# main.net
KiCad netlist of a schematic drawn in Altium Designer
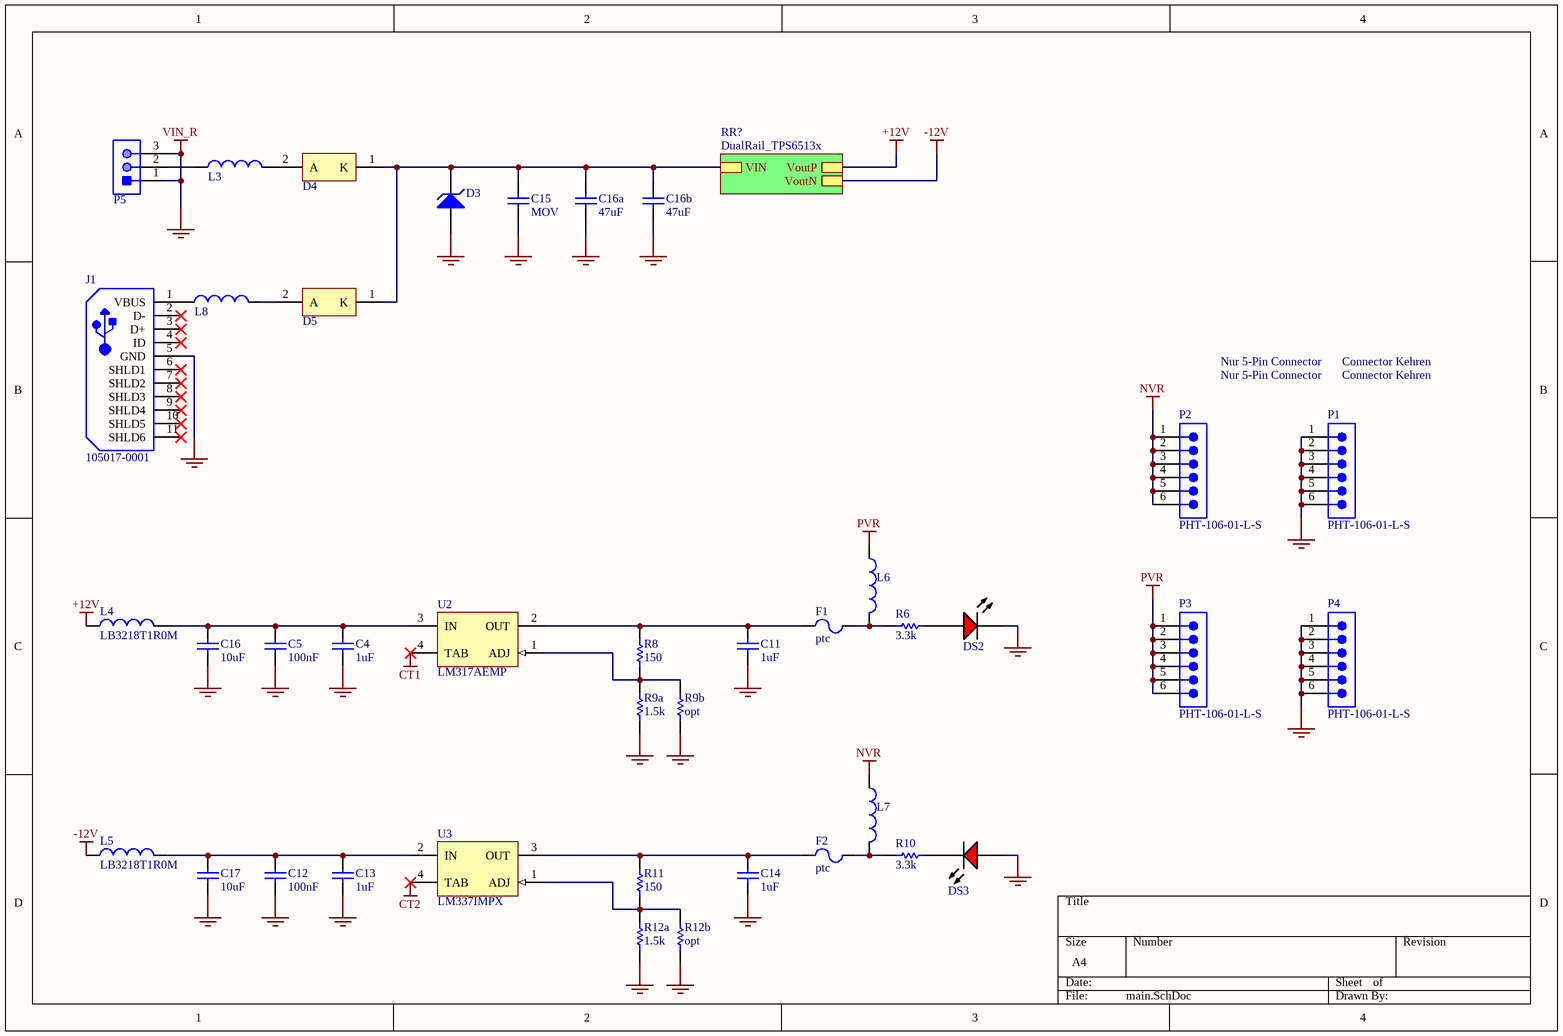
[diagram p0: main.SchDoc]

(export (version "E")
  (design (tool "Eeschema 10.0.6"))
  (components
    (comp (ref "C4")
      (value "1uF")
      (footprint "CAPC0603(1608)100_L")
      (description "CAP 1uF 25V ±20% 0603 (1608 Metric) Thickness 1mm SMD")
      (fields (field (name "TOLERANCE") "Â±20%"))
      (libsource (lib "Altium Content Vault") (part "CAP"))
    )
    (comp (ref "C5")
      (value "100nF")
      (footprint "CAPC0603(1608)100_L")
      (description "CAP 100nF 25V ±20% 0603 (1608 Metric) Thickness 1mm SMD")
      (fields (field (name "TOLERANCE") "Â±20%"))
      (libsource (lib "Altium Content Vault") (part "CAP"))
    )
    (comp (ref "C11")
      (value "1uF")
      (footprint "CAPC0603(1608)100_L")
      (description "CAP 1uF 25V ±20% 0603 (1608 Metric) Thickness 1mm SMD")
      (fields (field (name "TOLERANCE") "Â±20%"))
      (libsource (lib "Altium Content Vault") (part "CAP"))
    )
    (comp (ref "C12")
      (value "100nF")
      (footprint "CAPC0603(1608)100_L")
      (description "CAP 100nF 25V ±20% 0603 (1608 Metric) Thickness 1mm SMD")
      (fields (field (name "TOLERANCE") "Â±20%"))
      (libsource (lib "Altium Content Vault") (part "CAP"))
    )
    (comp (ref "C13")
      (value "1uF")
      (footprint "CAPC0603(1608)100_L")
      (description "CAP 1uF 25V ±20% 0603 (1608 Metric) Thickness 1mm SMD")
      (fields (field (name "TOLERANCE") "Â±20%"))
      (libsource (lib "Altium Content Vault") (part "CAP"))
    )
    (comp (ref "C14")
      (value "1uF")
      (footprint "CAPC0603(1608)100_L")
      (description "CAP 1uF 25V ±20% 0603 (1608 Metric) Thickness 1mm SMD")
      (fields (field (name "TOLERANCE") "Â±20%"))
      (libsource (lib "Altium Content Vault") (part "CAP"))
    )
    (comp (ref "C15")
      (value "MOV")
      (footprint "CAPC0805(2012)75_L")
      (description "MOV 0805")
      (fields (field (name "TOLERANCE") "Â±20%"))
      (libsource (lib "Altium Content Vault") (part "CAP"))
    )
    (comp (ref "C16")
      (value "10uF")
      (footprint "CAPC1206(3216)190_L")
      (description "CAP 4.7uF 25V ±20% 1206 (3216 Metric) Thickness 1.9mm SMD")
      (fields (field (name "TOLERANCE") "Â±20%"))
      (libsource (lib "Altium Content Vault") (part "CAP"))
    )
    (comp (ref "C16a")
      (value "47uF")
      (footprint "CAPC1206(3216)190_L")
      (description "CAP 47uF 10V ±20% 1206 X5R")
      (fields (field (name "TOLERANCE") "Â±20%"))
      (libsource (lib "Altium Content Vault") (part "CAP"))
    )
    (comp (ref "C16b")
      (value "47uF")
      (footprint "CAPC1206(3216)190_L")
      (description "CAP 47uF 10V ±20% 1206 X5R")
      (fields (field (name "TOLERANCE") "Â±20%"))
      (libsource (lib "Altium Content Vault") (part "CAP"))
    )
    (comp (ref "C17")
      (value "10uF")
      (footprint "CAPC1206(3216)190_L")
      (description "CAP 4.7uF 25V ±20% 1206 (3216 Metric) Thickness 1.9mm SMD")
      (fields (field (name "TOLERANCE") "Â±20%"))
      (libsource (lib "Altium Content Vault") (part "CAP"))
    )
    (comp (ref "D3")
      (value "Q6 - btz52c5v6")
      (footprint "DIOD-SOD123-2_V")
      (description "Zener Diode 500mw, 5.6v")
      (fields (field (name "MANUFACTURER") "Diodes Inc") (field (name "PARTNUMBER") "BZT52C16-7-F"))
      (libsource (lib "Altium Content Vault") (part "DIOD-DZEN-A1K2-2"))
    )
    (comp (ref "D4")
      (value "MBRM120LT3")
      (footprint "ONSC-POWERMITE-2-457-04_D_V")
      (description "Schottky Power Rectifier, 2-Pin Powermite, Tape and Reel")
      (fields (field (name "MANUFACTURER") "On Semiconductor"))
      (libsource (lib "Altium Content Vault") (part "ONSC-D-K1A2-2_A"))
    )
    (comp (ref "D5")
      (value "MBRM120LT3")
      (footprint "ONSC-POWERMITE-2-457-04_D_V")
      (description "Schottky Power Rectifier, 2-Pin Powermite, Tape and Reel")
      (fields (field (name "MANUFACTURER") "On Semiconductor"))
      (libsource (lib "Altium Content Vault") (part "ONSC-D-K1A2-2_A"))
    )
    (comp (ref "DS2")
      (value "TLMS1100-GS08")
      (footprint "VISH-TLMX1100_V")
      (description "LED, RED, 2.1 V, -40 to 100 degC, 2-Pin SMD (0603), RoHS, Tape and Reel")
      (fields (field (name "TOLERANCE") "5%"))
      (libsource (lib "Altium Content Vault") (part "LED-RED-AK-2"))
    )
    (comp (ref "DS3")
      (value "TLMS1100-GS08")
      (footprint "VISH-TLMX1100_V")
      (description "LED, RED, 2.1 V, -40 to 100 degC, 2-Pin SMD (0603), RoHS, Tape and Reel")
      (fields (field (name "TOLERANCE") "5%"))
      (libsource (lib "Altium Content Vault") (part "LED-RED-AK-2"))
    )
    (comp (ref "F1")
      (value "ptc")
      (footprint "LFUS-1206L012WR_V")
      (description "200mA PTC")
      (fields (field (name "MANUFACTURER") "Littelfuse"))
      (libsource (lib "Altium Content Vault") (part "FUSE-2"))
    )
    (comp (ref "F2")
      (value "ptc")
      (footprint "LFUS-1206L012WR_V")
      (description "200mA PTC")
      (fields (field (name "MANUFACTURER") "Littelfuse"))
      (libsource (lib "Altium Content Vault") (part "FUSE-2"))
    )
    (comp (ref "J1")
      (value "105017-0001")
      (footprint "USB-MICRO-B_V")
      (fields (field (name "MANUFACTURER") "Molex"))
      (libsource (lib "Altium Content Vault") (part "USB-5-6SHLD"))
    )
    (comp (ref "L3")
      (value "FBMJ2125HM210NT")
      (footprint "INDC2013X105X50LL20T30")
      (description "Chip Inductor, 21 Ohm, +/- 30%, 6 A, -40 to 125 degC, 0805 (2012 Metric), RoHS, Tape and Reel")
      (fields (field (name "TOLERANCE") "30%"))
      (libsource (lib "Altium Content Vault") (part "IND-2"))
    )
    (comp (ref "L4")
      (value "LB3218T1R0M")
      (footprint "TDK-B82422A1103K100_V")
      (description "FIXED IND 1UH 1.075A 60 MOHM SMD")
      (fields (field (name "TOLERANCE") "±10%") (field (name "MANUFACTURER") "EPCOS-(TDK)"))
      (libsource (lib "Altium Content Vault") (part "IND-2"))
    )
    (comp (ref "L5")
      (value "LB3218T1R0M")
      (footprint "TDK-B82422A1103K100_V")
      (description "FIXED IND 1UH 1.075A 60 MOHM SMD")
      (fields (field (name "TOLERANCE") "±10%") (field (name "MANUFACTURER") "EPCOS-(TDK)"))
      (libsource (lib "Altium Content Vault") (part "IND-2"))
    )
    (comp (ref "L6")
      (value "FBMJ2125HM210NT")
      (footprint "INDC2013X105X50LL20T30")
      (description "Chip Inductor, 21 Ohm, +/- 30%, 6 A, -40 to 125 degC, 0805 (2012 Metric), RoHS, Tape and Reel")
      (fields (field (name "TOLERANCE") "30%"))
      (libsource (lib "Altium Content Vault") (part "IND-2"))
    )
    (comp (ref "L7")
      (value "FBMJ2125HM210NT")
      (footprint "INDC2013X105X50LL20T30")
      (description "Chip Inductor, 21 Ohm, +/- 30%, 6 A, -40 to 125 degC, 0805 (2012 Metric), RoHS, Tape and Reel")
      (fields (field (name "TOLERANCE") "30%"))
      (libsource (lib "Altium Content Vault") (part "IND-2"))
    )
    (comp (ref "L8")
      (value "FBMJ2125HM210NT")
      (footprint "INDC2013X105X50LL20T30")
      (description "Chip Inductor, 21 Ohm, +/- 30%, 6 A, -40 to 125 degC, 0805 (2012 Metric), RoHS, Tape and Reel")
      (fields (field (name "TOLERANCE") "30%"))
      (libsource (lib "Altium Content Vault") (part "IND-2"))
    )
    (comp (ref "P1")
      (value "PHT-106-01-L-S")
      (footprint "SMTC-PHT-106-01-X-S")
      (description "Press Fit Header, Through-hole, Vertical, -55 to 125 degC, 2.54 mm Pitch, 6-Pin, Male, RoHS")
      (fields (field (name "MANUFACTURER") "Samtec"))
      (libsource (lib "Altium Content Vault") (part "SMTC-PHT-106-01-X-S"))
    )
    (comp (ref "P2")
      (value "PHT-106-01-L-S")
      (footprint "SMTC-PHT-106-01-X-S")
      (description "Press Fit Header, Through-hole, Vertical, -55 to 125 degC, 2.54 mm Pitch, 6-Pin, Male, RoHS")
      (fields (field (name "MANUFACTURER") "Samtec"))
      (libsource (lib "Altium Content Vault") (part "SMTC-PHT-106-01-X-S"))
    )
    (comp (ref "P3")
      (value "PHT-106-01-L-S")
      (footprint "SMTC-PHT-106-01-X-S")
      (description "Press Fit Header, Through-hole, Vertical, -55 to 125 degC, 2.54 mm Pitch, 6-Pin, Male, RoHS")
      (fields (field (name "MANUFACTURER") "Samtec"))
      (libsource (lib "Altium Content Vault") (part "SMTC-PHT-106-01-X-S"))
    )
    (comp (ref "P4")
      (value "PHT-106-01-L-S")
      (footprint "SMTC-PHT-106-01-X-S")
      (description "Press Fit Header, Through-hole, Vertical, -55 to 125 degC, 2.54 mm Pitch, 6-Pin, Male, RoHS")
      (fields (field (name "MANUFACTURER") "Samtec"))
      (libsource (lib "Altium Content Vault") (part "SMTC-PHT-106-01-X-S"))
    )
    (comp (ref "P5")
      (value "22-23-2031")
      (footprint "MOLX-22-23-2031_V")
      (description "Male Header, Pitch 2.54 mm, 1 x 3 Position, Height 8.18 mm, Tail Length 3.56 mm, RoHS, Bulk")
      (fields (field (name "MANUFACTURER") "Molex"))
      (libsource (lib "Altium Content Vault") (part "CN-1P-M-R3"))
    )
    (comp (ref "R6")
      (value "3.3k")
      (footprint "RESC0603(1608)_L")
      (fields (field (name "TOLERANCE") "1 %") (field (name "POWER") "0.1 W"))
      (libsource (lib "Altium Content Vault") (part "RES"))
    )
    (comp (ref "R8")
      (value "150")
      (footprint "RESC0603(1608)_L")
      (fields (field (name "TOLERANCE") "1 %") (field (name "POWER") "0.1 W"))
      (libsource (lib "Altium Content Vault") (part "RES"))
    )
    (comp (ref "R9a")
      (value "1.5k")
      (footprint "RESC0603(1608)_L")
      (fields (field (name "TOLERANCE") "1 %") (field (name "POWER") "0.1 W"))
      (libsource (lib "Altium Content Vault") (part "RES"))
    )
    (comp (ref "R9b")
      (value "opt")
      (footprint "RESC0603(1608)_L")
      (fields (field (name "TOLERANCE") "1 %") (field (name "POWER") "0.1 W"))
      (libsource (lib "Altium Content Vault") (part "RES"))
    )
    (comp (ref "R10")
      (value "3.3k")
      (footprint "RESC0603(1608)_L")
      (fields (field (name "TOLERANCE") "1 %") (field (name "POWER") "0.1 W"))
      (libsource (lib "Altium Content Vault") (part "RES"))
    )
    (comp (ref "R11")
      (value "150")
      (footprint "RESC0603(1608)_L")
      (fields (field (name "TOLERANCE") "1 %") (field (name "POWER") "0.1 W"))
      (libsource (lib "Altium Content Vault") (part "RES"))
    )
    (comp (ref "R12a")
      (value "1.5k")
      (footprint "RESC0603(1608)_L")
      (fields (field (name "TOLERANCE") "1 %") (field (name "POWER") "0.1 W"))
      (libsource (lib "Altium Content Vault") (part "RES"))
    )
    (comp (ref "R12b")
      (value "opt")
      (footprint "RESC0603(1608)_L")
      (fields (field (name "TOLERANCE") "1 %") (field (name "POWER") "0.1 W"))
      (libsource (lib "Altium Content Vault") (part "RES"))
    )
    (comp (ref "U2")
      (value "LM317AEMP")
      (footprint "DCY0004A_N")
      (description "3-Terminal Adjustable Regulator, 4-pin SOT-223")
      (fields (field (name "MANUFACTURER") "Texas Instruments"))
      (libsource (lib "Altium Content Vault") (part "PM-REG-LM317ADJ-SOT4"))
    )
    (comp (ref "U3")
      (value "LM337IMPX")
      (footprint "MP04A_N")
      (description "3-Terminal Adjustable Negative Regulator, 4-pin SOT-223")
      (fields (field (name "MANUFACTURER") "National Semiconductor"))
      (libsource (lib "Altium Content Vault") (part "PM-REG-LM337ADJ-SOT4"))
    )
  )
  (nets
    (net (code "1") (name "+12V") (class "Default")
      (node (ref "L4") (pin "1") (pinfunction "1_1") (pintype "passive"))
    )
    (net (code "2") (name "-12V") (class "Default")
      (node (ref "L5") (pin "1") (pinfunction "1_1") (pintype "passive"))
    )
    (net (code "3") (name "/VIN") (class "Default")
      (node (ref "C15") (pin "2") (pinfunction "2_2") (pintype "passive"))
      (node (ref "C16a") (pin "2") (pinfunction "2_2") (pintype "passive"))
      (node (ref "C16b") (pin "2") (pinfunction "2_2") (pintype "passive"))
      (node (ref "D3") (pin "2") (pinfunction "K_2") (pintype "passive"))
      (node (ref "D4") (pin "1") (pinfunction "K_1") (pintype "passive"))
      (node (ref "D5") (pin "1") (pinfunction "K_1") (pintype "passive"))
    )
    (net (code "4") (name "CT1") (class "Default")
      (node (ref "U2") (pin "4") (pinfunction "TAB_4") (pintype "power_in"))
    )
    (net (code "5") (name "CT2") (class "Default")
      (node (ref "U3") (pin "4") (pinfunction "TAB_4") (pintype "power_in"))
    )
    (net (code "6") (name "GND") (class "Default")
      (node (ref "C11") (pin "1") (pinfunction "1_1") (pintype "passive"))
      (node (ref "C12") (pin "1") (pinfunction "1_1") (pintype "passive"))
      (node (ref "C13") (pin "1") (pinfunction "1_1") (pintype "passive"))
      (node (ref "C14") (pin "1") (pinfunction "1_1") (pintype "passive"))
      (node (ref "C15") (pin "1") (pinfunction "1_1") (pintype "passive"))
      (node (ref "C16") (pin "1") (pinfunction "1_1") (pintype "passive"))
      (node (ref "C16a") (pin "1") (pinfunction "1_1") (pintype "passive"))
      (node (ref "C16b") (pin "1") (pinfunction "1_1") (pintype "passive"))
      (node (ref "C17") (pin "1") (pinfunction "1_1") (pintype "passive"))
      (node (ref "C4") (pin "1") (pinfunction "1_1") (pintype "passive"))
      (node (ref "C5") (pin "1") (pinfunction "1_1") (pintype "passive"))
      (node (ref "D3") (pin "1") (pinfunction "A_1") (pintype "passive"))
      (node (ref "DS2") (pin "2") (pinfunction "K_2") (pintype "passive"))
      (node (ref "DS3") (pin "1") (pinfunction "A_1") (pintype "passive"))
      (node (ref "J1") (pin "5") (pinfunction "GND_5") (pintype "passive"))
      (node (ref "P1") (pin "1") (pinfunction "1_1") (pintype "passive"))
      (node (ref "P1") (pin "2") (pinfunction "2_2") (pintype "passive"))
      (node (ref "P1") (pin "3") (pinfunction "3_3") (pintype "passive"))
      (node (ref "P1") (pin "4") (pinfunction "4_4") (pintype "passive"))
      (node (ref "P1") (pin "5") (pinfunction "5_5") (pintype "passive"))
      (node (ref "P1") (pin "6") (pinfunction "6_6") (pintype "passive"))
      (node (ref "P4") (pin "1") (pinfunction "1_1") (pintype "passive"))
      (node (ref "P4") (pin "2") (pinfunction "2_2") (pintype "passive"))
      (node (ref "P4") (pin "3") (pinfunction "3_3") (pintype "passive"))
      (node (ref "P4") (pin "4") (pinfunction "4_4") (pintype "passive"))
      (node (ref "P4") (pin "5") (pinfunction "5_5") (pintype "passive"))
      (node (ref "P4") (pin "6") (pinfunction "6_6") (pintype "passive"))
      (node (ref "P5") (pin "1") (pinfunction "1_1") (pintype "passive"))
      (node (ref "P5") (pin "3") (pinfunction "3_3") (pintype "passive"))
      (node (ref "R12a") (pin "2") (pinfunction "2_2") (pintype "passive"))
      (node (ref "R12b") (pin "2") (pinfunction "2_2") (pintype "passive"))
      (node (ref "R9a") (pin "2") (pinfunction "2_2") (pintype "passive"))
      (node (ref "R9b") (pin "2") (pinfunction "2_2") (pintype "passive"))
    )
    (net (code "7") (name "NVR") (class "Default")
      (node (ref "L7") (pin "1") (pinfunction "1_1") (pintype "passive"))
      (node (ref "P2") (pin "1") (pinfunction "1_1") (pintype "passive"))
      (node (ref "P2") (pin "2") (pinfunction "2_2") (pintype "passive"))
      (node (ref "P2") (pin "3") (pinfunction "3_3") (pintype "passive"))
      (node (ref "P2") (pin "4") (pinfunction "4_4") (pintype "passive"))
      (node (ref "P2") (pin "5") (pinfunction "5_5") (pintype "passive"))
      (node (ref "P2") (pin "6") (pinfunction "6_6") (pintype "passive"))
    )
    (net (code "8") (name "Net-(D4-A)") (class "Default")
      (node (ref "D4") (pin "2") (pinfunction "A_2") (pintype "passive"))
      (node (ref "L3") (pin "2") (pinfunction "2_2") (pintype "passive"))
    )
    (net (code "9") (name "Net-(D5-A)") (class "Default")
      (node (ref "D5") (pin "2") (pinfunction "A_2") (pintype "passive"))
      (node (ref "L8") (pin "2") (pinfunction "2_2") (pintype "passive"))
    )
    (net (code "10") (name "Net-(DS2-A)") (class "Default")
      (node (ref "DS2") (pin "1") (pinfunction "A_1") (pintype "passive"))
      (node (ref "R6") (pin "2") (pinfunction "2_2") (pintype "passive"))
    )
    (net (code "11") (name "Net-(DS3-K)") (class "Default")
      (node (ref "DS3") (pin "2") (pinfunction "K_2") (pintype "passive"))
      (node (ref "R10") (pin "2") (pinfunction "2_2") (pintype "passive"))
    )
    (net (code "12") (name "Net-(F1-Pad2)") (class "Default")
      (node (ref "F1") (pin "2") (pinfunction "2_2") (pintype "passive"))
      (node (ref "L6") (pin "2") (pinfunction "2_2") (pintype "passive"))
      (node (ref "R6") (pin "1") (pinfunction "1_1") (pintype "passive"))
    )
    (net (code "13") (name "Net-(F2-Pad2)") (class "Default")
      (node (ref "F2") (pin "2") (pinfunction "2_2") (pintype "passive"))
      (node (ref "L7") (pin "2") (pinfunction "2_2") (pintype "passive"))
      (node (ref "R10") (pin "1") (pinfunction "1_1") (pintype "passive"))
    )
    (net (code "14") (name "Net-(J1-VBUS)") (class "Default")
      (node (ref "J1") (pin "1") (pinfunction "VBUS_1") (pintype "passive"))
      (node (ref "L8") (pin "1") (pinfunction "1_1") (pintype "passive"))
    )
    (net (code "15") (name "Net-(L3-Pad1)") (class "Default")
      (node (ref "L3") (pin "1") (pinfunction "1_1") (pintype "passive"))
      (node (ref "P5") (pin "2") (pinfunction "2_2") (pintype "passive"))
    )
    (net (code "16") (name "Net-(U2-ADJ)") (class "Default")
      (node (ref "R8") (pin "2") (pinfunction "2_2") (pintype "passive"))
      (node (ref "R9a") (pin "1") (pinfunction "1_1") (pintype "passive"))
      (node (ref "R9b") (pin "1") (pinfunction "1_1") (pintype "passive"))
      (node (ref "U2") (pin "1") (pinfunction "ADJ_1") (pintype "input"))
    )
    (net (code "17") (name "Net-(U2-IN)") (class "Default")
      (node (ref "C16") (pin "2") (pinfunction "2_2") (pintype "passive"))
      (node (ref "C4") (pin "2") (pinfunction "2_2") (pintype "passive"))
      (node (ref "C5") (pin "2") (pinfunction "2_2") (pintype "passive"))
      (node (ref "L4") (pin "2") (pinfunction "2_2") (pintype "passive"))
      (node (ref "U2") (pin "3") (pinfunction "IN_3") (pintype "power_in"))
    )
    (net (code "18") (name "Net-(U2-OUT)") (class "Default")
      (node (ref "C11") (pin "2") (pinfunction "2_2") (pintype "passive"))
      (node (ref "F1") (pin "1") (pinfunction "1_1") (pintype "passive"))
      (node (ref "R8") (pin "1") (pinfunction "1_1") (pintype "passive"))
      (node (ref "U2") (pin "2") (pinfunction "OUT_2") (pintype "power_in"))
    )
    (net (code "19") (name "Net-(U3-ADJ)") (class "Default")
      (node (ref "R11") (pin "2") (pinfunction "2_2") (pintype "passive"))
      (node (ref "R12a") (pin "1") (pinfunction "1_1") (pintype "passive"))
      (node (ref "R12b") (pin "1") (pinfunction "1_1") (pintype "passive"))
      (node (ref "U3") (pin "1") (pinfunction "ADJ_1") (pintype "input"))
    )
    (net (code "20") (name "Net-(U3-IN)") (class "Default")
      (node (ref "C12") (pin "2") (pinfunction "2_2") (pintype "passive"))
      (node (ref "C13") (pin "2") (pinfunction "2_2") (pintype "passive"))
      (node (ref "C17") (pin "2") (pinfunction "2_2") (pintype "passive"))
      (node (ref "L5") (pin "2") (pinfunction "2_2") (pintype "passive"))
      (node (ref "U3") (pin "2") (pinfunction "IN_2") (pintype "power_in"))
    )
    (net (code "21") (name "Net-(U3-OUT)") (class "Default")
      (node (ref "C14") (pin "2") (pinfunction "2_2") (pintype "passive"))
      (node (ref "F2") (pin "1") (pinfunction "1_1") (pintype "passive"))
      (node (ref "R11") (pin "1") (pinfunction "1_1") (pintype "passive"))
      (node (ref "U3") (pin "3") (pinfunction "OUT_3") (pintype "power_in"))
    )
    (net (code "22") (name "PVR") (class "Default")
      (node (ref "L6") (pin "1") (pinfunction "1_1") (pintype "passive"))
      (node (ref "P3") (pin "1") (pinfunction "1_1") (pintype "passive"))
      (node (ref "P3") (pin "2") (pinfunction "2_2") (pintype "passive"))
      (node (ref "P3") (pin "3") (pinfunction "3_3") (pintype "passive"))
      (node (ref "P3") (pin "4") (pinfunction "4_4") (pintype "passive"))
      (node (ref "P3") (pin "5") (pinfunction "5_5") (pintype "passive"))
      (node (ref "P3") (pin "6") (pinfunction "6_6") (pintype "passive"))
    )
    (net (code "23") (name "unconnected-(J1-D+-Pad3)") (class "Default")
      (node (ref "J1") (pin "3") (pinfunction "D+_3") (pintype "passive+no_connect"))
    )
    (net (code "24") (name "unconnected-(J1-D--Pad2)") (class "Default")
      (node (ref "J1") (pin "2") (pinfunction "D-_2") (pintype "passive+no_connect"))
    )
    (net (code "25") (name "unconnected-(J1-ID-Pad4)") (class "Default")
      (node (ref "J1") (pin "4") (pinfunction "ID_4") (pintype "passive+no_connect"))
    )
    (net (code "26") (name "unconnected-(J1-SHLD1-Pad6)") (class "Default")
      (node (ref "J1") (pin "6") (pinfunction "SHLD1_6") (pintype "passive+no_connect"))
    )
    (net (code "27") (name "unconnected-(J1-SHLD2-Pad7)") (class "Default")
      (node (ref "J1") (pin "7") (pinfunction "SHLD2_7") (pintype "passive+no_connect"))
    )
    (net (code "28") (name "unconnected-(J1-SHLD3-Pad8)") (class "Default")
      (node (ref "J1") (pin "8") (pinfunction "SHLD3_8") (pintype "passive+no_connect"))
    )
    (net (code "29") (name "unconnected-(J1-SHLD4-Pad9)") (class "Default")
      (node (ref "J1") (pin "9") (pinfunction "SHLD4_9") (pintype "passive+no_connect"))
    )
    (net (code "30") (name "unconnected-(J1-SHLD5-Pad10)") (class "Default")
      (node (ref "J1") (pin "10") (pinfunction "SHLD5_10") (pintype "passive+no_connect"))
    )
    (net (code "31") (name "unconnected-(J1-SHLD6-Pad11)") (class "Default")
      (node (ref "J1") (pin "11") (pinfunction "SHLD6_11") (pintype "passive+no_connect"))
    )
  )
)
